# top.net
KiCad netlist of a schematic drawn in Altium Designer
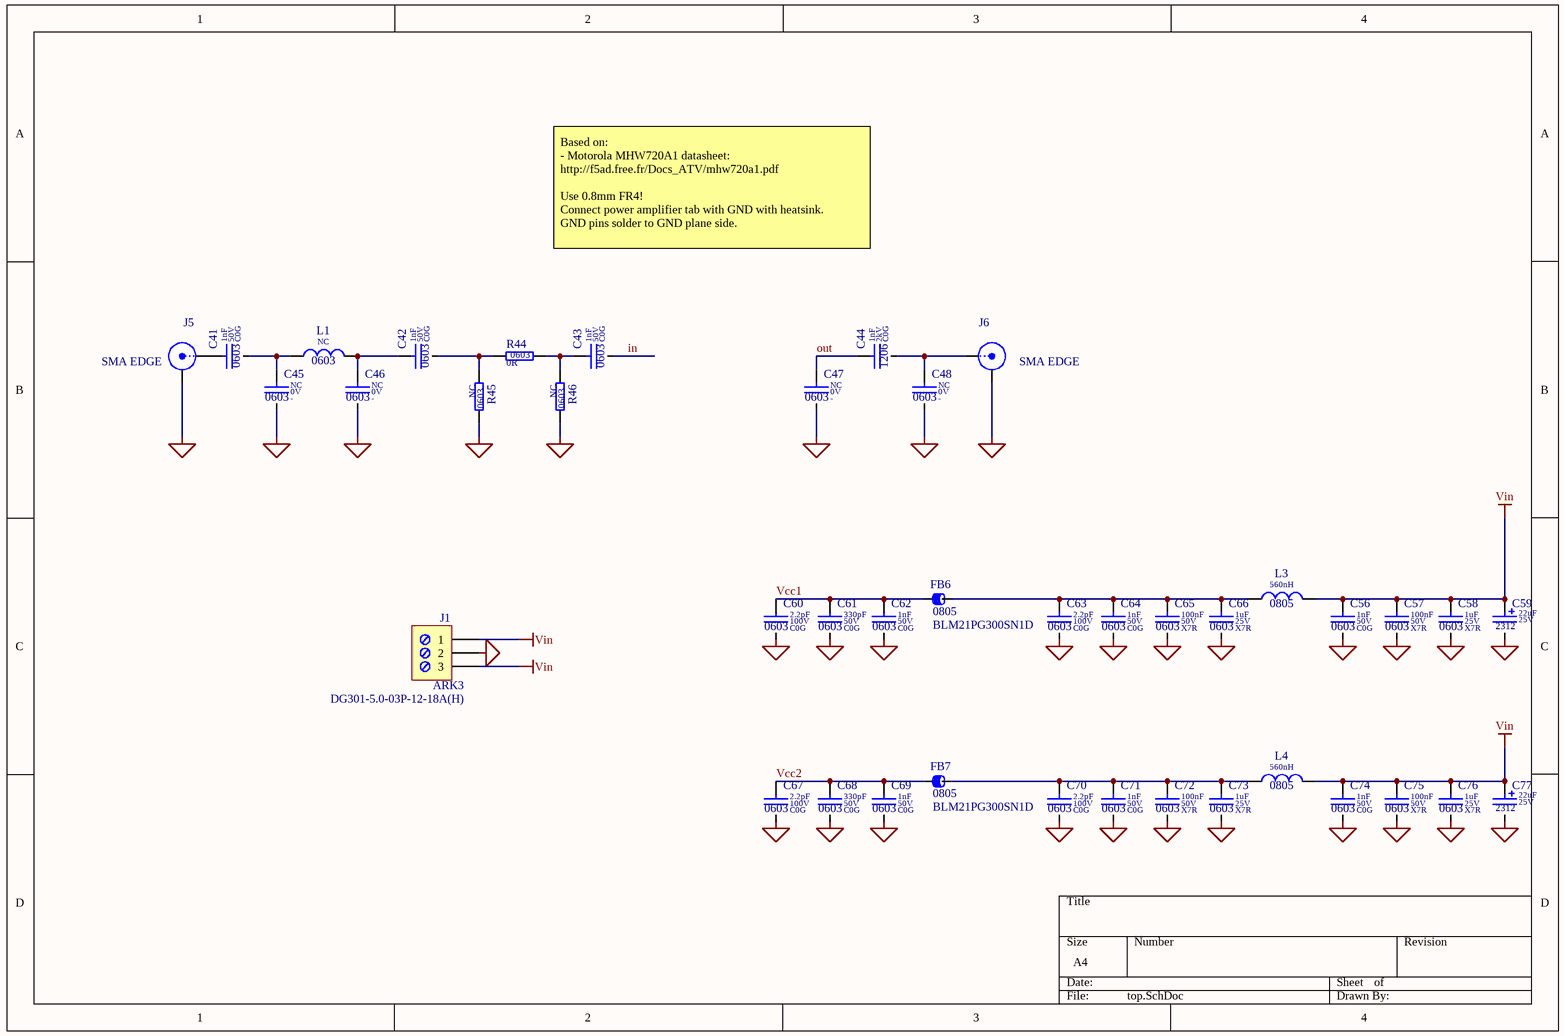
[diagram p0: top.SchDoc]

(export (version "E")
  (design (tool "Eeschema 10.0.6"))
  (components
    (comp (ref "C41")
      (value "1nF")
      (footprint "C_0603_1608")
      (description "Capacitor")
      (fields
        (field (name "DIELECTRIC") "C0G")
        (field (name "VOLTAGE") "50V")
        (field (name "SCH_FOOTPRINT") "0603")
        (field (name "PART NUMBER") "C_1nF_50V_C0G_0603_5")
        (field (name "MANUFACTURER") "Samsung")
      )
      (libsource (lib "Library") (part "C"))
    )
    (comp (ref "C42")
      (value "1nF")
      (footprint "C_0603_1608")
      (description "Capacitor")
      (fields
        (field (name "DIELECTRIC") "C0G")
        (field (name "VOLTAGE") "50V")
        (field (name "SCH_FOOTPRINT") "0603")
        (field (name "PART NUMBER") "C_1nF_50V_C0G_0603_5")
        (field (name "MANUFACTURER") "Samsung")
      )
      (libsource (lib "Library") (part "C"))
    )
    (comp (ref "C43")
      (value "1nF")
      (footprint "C_0603_1608")
      (description "Capacitor")
      (fields
        (field (name "DIELECTRIC") "C0G")
        (field (name "VOLTAGE") "50V")
        (field (name "SCH_FOOTPRINT") "0603")
        (field (name "PART NUMBER") "C_1nF_50V_C0G_0603_5")
        (field (name "MANUFACTURER") "Samsung")
      )
      (libsource (lib "Library") (part "C"))
    )
    (comp (ref "C44")
      (value "1nF")
      (footprint "C_1206_3216")
      (description "Capacitor")
      (fields
        (field (name "DIELECTRIC") "C0G")
        (field (name "VOLTAGE") "2kV")
        (field (name "SCH_FOOTPRINT") "1206")
        (field (name "PART NUMBER") "C_1nF_2kV_C0G_1206_10")
        (field (name "MANUFACTURER") "AVX")
      )
      (libsource (lib "Library") (part "C"))
    )
    (comp (ref "C45")
      (value "NC")
      (footprint "C_NC_0603_1608")
      (description "Capacitor")
      (fields
        (field (name "DIELECTRIC") "-")
        (field (name "VOLTAGE") "0V")
        (field (name "SCH_FOOTPRINT") "0603")
        (field (name "PART NUMBER") "C_GENERIC_0603")
      )
      (libsource (lib "Library") (part "C"))
    )
    (comp (ref "C46")
      (value "NC")
      (footprint "C_NC_0603_1608")
      (description "Capacitor")
      (fields
        (field (name "DIELECTRIC") "-")
        (field (name "VOLTAGE") "0V")
        (field (name "SCH_FOOTPRINT") "0603")
        (field (name "PART NUMBER") "C_GENERIC_0603")
      )
      (libsource (lib "Library") (part "C"))
    )
    (comp (ref "C47")
      (value "NC")
      (footprint "C_NC_0603_1608")
      (description "Capacitor")
      (fields
        (field (name "DIELECTRIC") "-")
        (field (name "VOLTAGE") "0V")
        (field (name "SCH_FOOTPRINT") "0603")
        (field (name "PART NUMBER") "C_GENERIC_0603")
      )
      (libsource (lib "Library") (part "C"))
    )
    (comp (ref "C48")
      (value "NC")
      (footprint "C_NC_0603_1608")
      (description "Capacitor")
      (fields
        (field (name "DIELECTRIC") "-")
        (field (name "VOLTAGE") "0V")
        (field (name "SCH_FOOTPRINT") "0603")
        (field (name "PART NUMBER") "C_GENERIC_0603")
      )
      (libsource (lib "Library") (part "C"))
    )
    (comp (ref "C56")
      (value "1nF")
      (footprint "C_0603_1608")
      (description "Capacitor")
      (fields
        (field (name "DIELECTRIC") "C0G")
        (field (name "VOLTAGE") "50V")
        (field (name "SCH_FOOTPRINT") "0603")
        (field (name "PART NUMBER") "C_1nF_50V_C0G_0603_5")
        (field (name "MANUFACTURER") "Samsung")
      )
      (libsource (lib "Library") (part "C"))
    )
    (comp (ref "C57")
      (value "100nF")
      (footprint "C_0603_1608")
      (description "Capacitor")
      (fields
        (field (name "DIELECTRIC") "X7R")
        (field (name "VOLTAGE") "50V")
        (field (name "SCH_FOOTPRINT") "0603")
        (field (name "PART NUMBER") "C_100nF_50V_X7R_0603_5")
        (field (name "MANUFACTURER") "Samsung")
      )
      (libsource (lib "Library") (part "C"))
    )
    (comp (ref "C58")
      (value "1uF")
      (footprint "C_0603_1608")
      (description "Capacitor")
      (fields
        (field (name "DIELECTRIC") "X7R")
        (field (name "VOLTAGE") "25V")
        (field (name "SCH_FOOTPRINT") "0603")
        (field (name "PART NUMBER") "C_1uF_25V_X7R_0603_10")
        (field (name "MANUFACTURER") "Samsung")
      )
      (libsource (lib "Library") (part "C"))
    )
    (comp (ref "C59")
      (value "22uF")
      (footprint "CT_2312_6032")
      (description "Capacitor")
      (fields
        (field (name "SCH_FOOTPRINT") "2312")
        (field (name "VOLTAGE") "25V")
        (field (name "PART NUMBER") "CT_22uF_16V_TA2O5_2312_10")
        (field (name "MANUFACTURER") "Kemet")
      )
      (libsource (lib "Library") (part "CT"))
    )
    (comp (ref "C60")
      (value "2.2pF")
      (footprint "C_0603_1608")
      (description "Capacitor")
      (fields
        (field (name "DIELECTRIC") "C0G")
        (field (name "VOLTAGE") "100V")
        (field (name "SCH_FOOTPRINT") "0603")
        (field (name "PART NUMBER") "C_2.2pF_100V_C0G_0603_5")
        (field (name "MANUFACTURER") "AVX")
      )
      (libsource (lib "Library") (part "C"))
    )
    (comp (ref "C61")
      (value "330pF")
      (footprint "C_0603_1608")
      (description "Capacitor")
      (fields
        (field (name "DIELECTRIC") "C0G")
        (field (name "VOLTAGE") "50V")
        (field (name "SCH_FOOTPRINT") "0603")
        (field (name "PART NUMBER") "C_330pF_50V_C0G_0603_5")
        (field (name "MANUFACTURER") "Murata")
      )
      (libsource (lib "Library") (part "C"))
    )
    (comp (ref "C62")
      (value "1nF")
      (footprint "C_0603_1608")
      (description "Capacitor")
      (fields
        (field (name "DIELECTRIC") "C0G")
        (field (name "VOLTAGE") "50V")
        (field (name "SCH_FOOTPRINT") "0603")
        (field (name "PART NUMBER") "C_1nF_50V_C0G_0603_5")
        (field (name "MANUFACTURER") "Samsung")
      )
      (libsource (lib "Library") (part "C"))
    )
    (comp (ref "C63")
      (value "2.2pF")
      (footprint "C_0603_1608")
      (description "Capacitor")
      (fields
        (field (name "DIELECTRIC") "C0G")
        (field (name "VOLTAGE") "100V")
        (field (name "SCH_FOOTPRINT") "0603")
        (field (name "PART NUMBER") "C_2.2pF_100V_C0G_0603_5")
        (field (name "MANUFACTURER") "AVX")
      )
      (libsource (lib "Library") (part "C"))
    )
    (comp (ref "C64")
      (value "1nF")
      (footprint "C_0603_1608")
      (description "Capacitor")
      (fields
        (field (name "DIELECTRIC") "C0G")
        (field (name "VOLTAGE") "50V")
        (field (name "SCH_FOOTPRINT") "0603")
        (field (name "PART NUMBER") "C_1nF_50V_C0G_0603_5")
        (field (name "MANUFACTURER") "Samsung")
      )
      (libsource (lib "Library") (part "C"))
    )
    (comp (ref "C65")
      (value "100nF")
      (footprint "C_0603_1608")
      (description "Capacitor")
      (fields
        (field (name "DIELECTRIC") "X7R")
        (field (name "VOLTAGE") "50V")
        (field (name "SCH_FOOTPRINT") "0603")
        (field (name "PART NUMBER") "C_100nF_50V_X7R_0603_5")
        (field (name "MANUFACTURER") "Samsung")
      )
      (libsource (lib "Library") (part "C"))
    )
    (comp (ref "C66")
      (value "1uF")
      (footprint "C_0603_1608")
      (description "Capacitor")
      (fields
        (field (name "DIELECTRIC") "X7R")
        (field (name "VOLTAGE") "25V")
        (field (name "SCH_FOOTPRINT") "0603")
        (field (name "PART NUMBER") "C_1uF_25V_X7R_0603_10")
        (field (name "MANUFACTURER") "Samsung")
      )
      (libsource (lib "Library") (part "C"))
    )
    (comp (ref "C67")
      (value "2.2pF")
      (footprint "C_0603_1608")
      (description "Capacitor")
      (fields
        (field (name "DIELECTRIC") "C0G")
        (field (name "VOLTAGE") "100V")
        (field (name "SCH_FOOTPRINT") "0603")
        (field (name "PART NUMBER") "C_2.2pF_100V_C0G_0603_5")
        (field (name "MANUFACTURER") "AVX")
      )
      (libsource (lib "Library") (part "C"))
    )
    (comp (ref "C68")
      (value "330pF")
      (footprint "C_0603_1608")
      (description "Capacitor")
      (fields
        (field (name "DIELECTRIC") "C0G")
        (field (name "VOLTAGE") "50V")
        (field (name "SCH_FOOTPRINT") "0603")
        (field (name "PART NUMBER") "C_330pF_50V_C0G_0603_5")
        (field (name "MANUFACTURER") "Murata")
      )
      (libsource (lib "Library") (part "C"))
    )
    (comp (ref "C69")
      (value "1nF")
      (footprint "C_0603_1608")
      (description "Capacitor")
      (fields
        (field (name "DIELECTRIC") "C0G")
        (field (name "VOLTAGE") "50V")
        (field (name "SCH_FOOTPRINT") "0603")
        (field (name "PART NUMBER") "C_1nF_50V_C0G_0603_5")
        (field (name "MANUFACTURER") "Samsung")
      )
      (libsource (lib "Library") (part "C"))
    )
    (comp (ref "C70")
      (value "2.2pF")
      (footprint "C_0603_1608")
      (description "Capacitor")
      (fields
        (field (name "DIELECTRIC") "C0G")
        (field (name "VOLTAGE") "100V")
        (field (name "SCH_FOOTPRINT") "0603")
        (field (name "PART NUMBER") "C_2.2pF_100V_C0G_0603_5")
        (field (name "MANUFACTURER") "AVX")
      )
      (libsource (lib "Library") (part "C"))
    )
    (comp (ref "C71")
      (value "1nF")
      (footprint "C_0603_1608")
      (description "Capacitor")
      (fields
        (field (name "DIELECTRIC") "C0G")
        (field (name "VOLTAGE") "50V")
        (field (name "SCH_FOOTPRINT") "0603")
        (field (name "PART NUMBER") "C_1nF_50V_C0G_0603_5")
        (field (name "MANUFACTURER") "Samsung")
      )
      (libsource (lib "Library") (part "C"))
    )
    (comp (ref "C72")
      (value "100nF")
      (footprint "C_0603_1608")
      (description "Capacitor")
      (fields
        (field (name "DIELECTRIC") "X7R")
        (field (name "VOLTAGE") "50V")
        (field (name "SCH_FOOTPRINT") "0603")
        (field (name "PART NUMBER") "C_100nF_50V_X7R_0603_5")
        (field (name "MANUFACTURER") "Samsung")
      )
      (libsource (lib "Library") (part "C"))
    )
    (comp (ref "C73")
      (value "1uF")
      (footprint "C_0603_1608")
      (description "Capacitor")
      (fields
        (field (name "DIELECTRIC") "X7R")
        (field (name "VOLTAGE") "25V")
        (field (name "SCH_FOOTPRINT") "0603")
        (field (name "PART NUMBER") "C_1uF_25V_X7R_0603_10")
        (field (name "MANUFACTURER") "Samsung")
      )
      (libsource (lib "Library") (part "C"))
    )
    (comp (ref "C74")
      (value "1nF")
      (footprint "C_0603_1608")
      (description "Capacitor")
      (fields
        (field (name "DIELECTRIC") "C0G")
        (field (name "VOLTAGE") "50V")
        (field (name "SCH_FOOTPRINT") "0603")
        (field (name "PART NUMBER") "C_1nF_50V_C0G_0603_5")
        (field (name "MANUFACTURER") "Samsung")
      )
      (libsource (lib "Library") (part "C"))
    )
    (comp (ref "C75")
      (value "100nF")
      (footprint "C_0603_1608")
      (description "Capacitor")
      (fields
        (field (name "DIELECTRIC") "X7R")
        (field (name "VOLTAGE") "50V")
        (field (name "SCH_FOOTPRINT") "0603")
        (field (name "PART NUMBER") "C_100nF_50V_X7R_0603_5")
        (field (name "MANUFACTURER") "Samsung")
      )
      (libsource (lib "Library") (part "C"))
    )
    (comp (ref "C76")
      (value "1uF")
      (footprint "C_0603_1608")
      (description "Capacitor")
      (fields
        (field (name "DIELECTRIC") "X7R")
        (field (name "VOLTAGE") "25V")
        (field (name "SCH_FOOTPRINT") "0603")
        (field (name "PART NUMBER") "C_1uF_25V_X7R_0603_10")
        (field (name "MANUFACTURER") "Samsung")
      )
      (libsource (lib "Library") (part "C"))
    )
    (comp (ref "C77")
      (value "22uF")
      (footprint "CT_2312_6032")
      (description "Capacitor")
      (fields
        (field (name "SCH_FOOTPRINT") "2312")
        (field (name "VOLTAGE") "25V")
        (field (name "PART NUMBER") "CT_22uF_16V_TA2O5_2312_10")
        (field (name "MANUFACTURER") "Kemet")
      )
      (libsource (lib "Library") (part "CT"))
    )
    (comp (ref "FB6")
      (value "BLM21PG300SN1D")
      (footprint "FB_0805_2012")
      (description "Ferrite Bead")
      (fields
        (field (name "PART NUMBER") "FB_BLM21PG300SN1D")
        (field (name "SCH_FOOTPRINT") "0805")
        (field (name "MANUFACTURER") "Murata")
      )
      (libsource (lib "Library") (part "FB"))
    )
    (comp (ref "FB7")
      (value "BLM21PG300SN1D")
      (footprint "FB_0805_2012")
      (description "Ferrite Bead")
      (fields
        (field (name "PART NUMBER") "FB_BLM21PG300SN1D")
        (field (name "SCH_FOOTPRINT") "0805")
        (field (name "MANUFACTURER") "Murata")
      )
      (libsource (lib "Library") (part "FB"))
    )
    (comp (ref "J1")
      (value "DG301-5.0-03P-12-18A(H)")
      (footprint "J_ARK3")
      (description "ARK Screw terminal, 3-Pin")
      (fields
        (field (name "SCH_FOOTPRINT") "ARK3")
        (field (name "PART NUMBER") "J_TB-5.0-P-3P")
        (field (name "MANUFACTURER") "DEGSON ELECTRONICS")
      )
      (libsource (lib "Library") (part "J_ARK3"))
    )
    (comp (ref "J5")
      (value "SMA EDGE")
      (footprint "J_SMA_EDGE")
      (description "SMA connector")
      (fields (field (name "PART NUMBER") "J_SMA_EDGE_UNIVERSAL") (field (name "SCH_FOOTPRINT") "SMA EDGE"))
      (libsource (lib "Library") (part "J_SMA"))
    )
    (comp (ref "J6")
      (value "SMA EDGE")
      (footprint "J_SMA_EDGE")
      (description "SMA connector")
      (fields (field (name "PART NUMBER") "J_SMA_EDGE_UNIVERSAL") (field (name "SCH_FOOTPRINT") "SMA EDGE"))
      (libsource (lib "Library") (part "J_SMA"))
    )
    (comp (ref "L1")
      (value "NC")
      (footprint "L_NC_0603_1608")
      (description "Induction")
      (fields (field (name "SCH_FOOTPRINT") "0603") (field (name "PART NUMBER") "L_0603"))
      (libsource (lib "Library") (part "L"))
    )
    (comp (ref "L3")
      (value "560nH")
      (footprint "L_0805_2012")
      (description "Induction")
      (fields
        (field (name "SCH_FOOTPRINT") "0805")
        (field (name "PART NUMBER") "L_560nH_1.7A_0805")
        (field (name "MANUFACTURER") "Wurth")
      )
      (libsource (lib "Library") (part "L"))
    )
    (comp (ref "L4")
      (value "560nH")
      (footprint "L_0805_2012")
      (description "Induction")
      (fields
        (field (name "SCH_FOOTPRINT") "0805")
        (field (name "PART NUMBER") "L_560nH_1.7A_0805")
        (field (name "MANUFACTURER") "Wurth")
      )
      (libsource (lib "Library") (part "L"))
    )
    (comp (ref "R44")
      (value "0R")
      (footprint "R_0603_1608")
      (fields
        (field (name "SCH_FOOTPRINT") "0603")
        (field (name "PART NUMBER") "R_0R_0603_5")
        (field (name "VOLTAGE") "50V")
        (field (name "POWER") "100mW")
      )
      (libsource (lib "Library") (part "R"))
    )
    (comp (ref "R45")
      (value "NC")
      (footprint "R_NC_0603_1608")
      (fields
        (field (name "SCH_FOOTPRINT") "0603")
        (field (name "PART NUMBER") "R_GENERIC_0603")
        (field (name "Comment") "Resistor")
      )
      (libsource (lib "Library") (part "R"))
    )
    (comp (ref "R46")
      (value "NC")
      (footprint "R_NC_0603_1608")
      (fields
        (field (name "SCH_FOOTPRINT") "0603")
        (field (name "PART NUMBER") "R_GENERIC_0603")
        (field (name "Comment") "Resistor")
      )
      (libsource (lib "Library") (part "R"))
    )
  )
  (nets
    (net (code "1") (name "/Vcc1") (class "Default")
      (node (ref "C60") (pin "1") (pinfunction "1_1") (pintype "passive"))
      (node (ref "C61") (pin "1") (pinfunction "1_1") (pintype "passive"))
      (node (ref "C62") (pin "1") (pinfunction "1_1") (pintype "passive"))
      (node (ref "FB6") (pin "1") (pintype "passive"))
    )
    (net (code "2") (name "/Vcc2") (class "Default")
      (node (ref "C67") (pin "1") (pinfunction "1_1") (pintype "passive"))
      (node (ref "C68") (pin "1") (pinfunction "1_1") (pintype "passive"))
      (node (ref "C69") (pin "1") (pinfunction "1_1") (pintype "passive"))
      (node (ref "FB7") (pin "1") (pintype "passive"))
    )
    (net (code "3") (name "/in") (class "Default")
      (node (ref "C43") (pin "2") (pinfunction "2_2") (pintype "passive"))
    )
    (net (code "4") (name "/out") (class "Default")
      (node (ref "C44") (pin "1") (pinfunction "1_1") (pintype "passive"))
      (node (ref "C47") (pin "1") (pinfunction "1_1") (pintype "passive"))
    )
    (net (code "5") (name "GND") (class "Default")
      (node (ref "C45") (pin "2") (pinfunction "2_2") (pintype "passive"))
      (node (ref "C46") (pin "2") (pinfunction "2_2") (pintype "passive"))
      (node (ref "C47") (pin "2") (pinfunction "2_2") (pintype "passive"))
      (node (ref "C48") (pin "2") (pinfunction "2_2") (pintype "passive"))
      (node (ref "C56") (pin "2") (pinfunction "2_2") (pintype "passive"))
      (node (ref "C57") (pin "2") (pinfunction "2_2") (pintype "passive"))
      (node (ref "C58") (pin "2") (pinfunction "2_2") (pintype "passive"))
      (node (ref "C59") (pin "2") (pinfunction "2_2") (pintype "passive"))
      (node (ref "C60") (pin "2") (pinfunction "2_2") (pintype "passive"))
      (node (ref "C61") (pin "2") (pinfunction "2_2") (pintype "passive"))
      (node (ref "C62") (pin "2") (pinfunction "2_2") (pintype "passive"))
      (node (ref "C63") (pin "2") (pinfunction "2_2") (pintype "passive"))
      (node (ref "C64") (pin "2") (pinfunction "2_2") (pintype "passive"))
      (node (ref "C65") (pin "2") (pinfunction "2_2") (pintype "passive"))
      (node (ref "C66") (pin "2") (pinfunction "2_2") (pintype "passive"))
      (node (ref "C67") (pin "2") (pinfunction "2_2") (pintype "passive"))
      (node (ref "C68") (pin "2") (pinfunction "2_2") (pintype "passive"))
      (node (ref "C69") (pin "2") (pinfunction "2_2") (pintype "passive"))
      (node (ref "C70") (pin "2") (pinfunction "2_2") (pintype "passive"))
      (node (ref "C71") (pin "2") (pinfunction "2_2") (pintype "passive"))
      (node (ref "C72") (pin "2") (pinfunction "2_2") (pintype "passive"))
      (node (ref "C73") (pin "2") (pinfunction "2_2") (pintype "passive"))
      (node (ref "C74") (pin "2") (pinfunction "2_2") (pintype "passive"))
      (node (ref "C75") (pin "2") (pinfunction "2_2") (pintype "passive"))
      (node (ref "C76") (pin "2") (pinfunction "2_2") (pintype "passive"))
      (node (ref "C77") (pin "2") (pinfunction "2_2") (pintype "passive"))
      (node (ref "J1") (pin "2") (pinfunction "2_2") (pintype "passive"))
      (node (ref "J5") (pin "2") (pinfunction "GND_2") (pintype "power_in"))
      (node (ref "J6") (pin "2") (pinfunction "GND_2") (pintype "power_in"))
      (node (ref "R45") (pin "2") (pinfunction "2_2") (pintype "passive"))
      (node (ref "R46") (pin "2") (pinfunction "2_2") (pintype "passive"))
    )
    (net (code "6") (name "Net-(C41-Pad2)") (class "Default")
      (node (ref "C41") (pin "2") (pinfunction "2_2") (pintype "passive"))
      (node (ref "C45") (pin "1") (pinfunction "1_1") (pintype "passive"))
      (node (ref "L1") (pin "1") (pinfunction "1_1") (pintype "passive"))
    )
    (net (code "7") (name "Net-(C42-Pad1)") (class "Default")
      (node (ref "C42") (pin "1") (pinfunction "1_1") (pintype "passive"))
      (node (ref "C46") (pin "1") (pinfunction "1_1") (pintype "passive"))
      (node (ref "L1") (pin "2") (pinfunction "2_2") (pintype "passive"))
    )
    (net (code "8") (name "Net-(C42-Pad2)") (class "Default")
      (node (ref "C42") (pin "2") (pinfunction "2_2") (pintype "passive"))
      (node (ref "R44") (pin "1") (pinfunction "1_1") (pintype "passive"))
      (node (ref "R45") (pin "1") (pinfunction "1_1") (pintype "passive"))
    )
    (net (code "9") (name "Net-(C43-Pad1)") (class "Default")
      (node (ref "C43") (pin "1") (pinfunction "1_1") (pintype "passive"))
      (node (ref "R44") (pin "2") (pinfunction "2_2") (pintype "passive"))
      (node (ref "R46") (pin "1") (pinfunction "1_1") (pintype "passive"))
    )
    (net (code "10") (name "Net-(C63-Pad1)") (class "Default")
      (node (ref "C63") (pin "1") (pinfunction "1_1") (pintype "passive"))
      (node (ref "C64") (pin "1") (pinfunction "1_1") (pintype "passive"))
      (node (ref "C65") (pin "1") (pinfunction "1_1") (pintype "passive"))
      (node (ref "C66") (pin "1") (pinfunction "1_1") (pintype "passive"))
      (node (ref "FB6") (pin "2") (pintype "passive"))
      (node (ref "L3") (pin "1") (pinfunction "1_1") (pintype "passive"))
    )
    (net (code "11") (name "Net-(C70-Pad1)") (class "Default")
      (node (ref "C70") (pin "1") (pinfunction "1_1") (pintype "passive"))
      (node (ref "C71") (pin "1") (pinfunction "1_1") (pintype "passive"))
      (node (ref "C72") (pin "1") (pinfunction "1_1") (pintype "passive"))
      (node (ref "C73") (pin "1") (pinfunction "1_1") (pintype "passive"))
      (node (ref "FB7") (pin "2") (pintype "passive"))
      (node (ref "L4") (pin "1") (pinfunction "1_1") (pintype "passive"))
    )
    (net (code "12") (name "Net-(J5-X)") (class "Default")
      (node (ref "C41") (pin "1") (pinfunction "1_1") (pintype "passive"))
      (node (ref "J5") (pin "1") (pinfunction "X_1") (pintype "passive"))
    )
    (net (code "13") (name "Net-(J6-X)") (class "Default")
      (node (ref "C44") (pin "2") (pinfunction "2_2") (pintype "passive"))
      (node (ref "C48") (pin "1") (pinfunction "1_1") (pintype "passive"))
      (node (ref "J6") (pin "1") (pinfunction "X_1") (pintype "passive"))
    )
    (net (code "14") (name "Vin") (class "Default")
      (node (ref "C56") (pin "1") (pinfunction "1_1") (pintype "passive"))
      (node (ref "C57") (pin "1") (pinfunction "1_1") (pintype "passive"))
      (node (ref "C58") (pin "1") (pinfunction "1_1") (pintype "passive"))
      (node (ref "C59") (pin "1") (pinfunction "1_1") (pintype "passive"))
      (node (ref "C74") (pin "1") (pinfunction "1_1") (pintype "passive"))
      (node (ref "C75") (pin "1") (pinfunction "1_1") (pintype "passive"))
      (node (ref "C76") (pin "1") (pinfunction "1_1") (pintype "passive"))
      (node (ref "C77") (pin "1") (pinfunction "1_1") (pintype "passive"))
      (node (ref "J1") (pin "1") (pinfunction "1_1") (pintype "passive"))
      (node (ref "J1") (pin "3") (pinfunction "3_3") (pintype "passive"))
      (node (ref "L3") (pin "2") (pinfunction "2_2") (pintype "passive"))
      (node (ref "L4") (pin "2") (pinfunction "2_2") (pintype "passive"))
    )
  )
)
